# EasyEDA_Schematic.net
KiCad netlist of a schematic drawn in EasyEDA
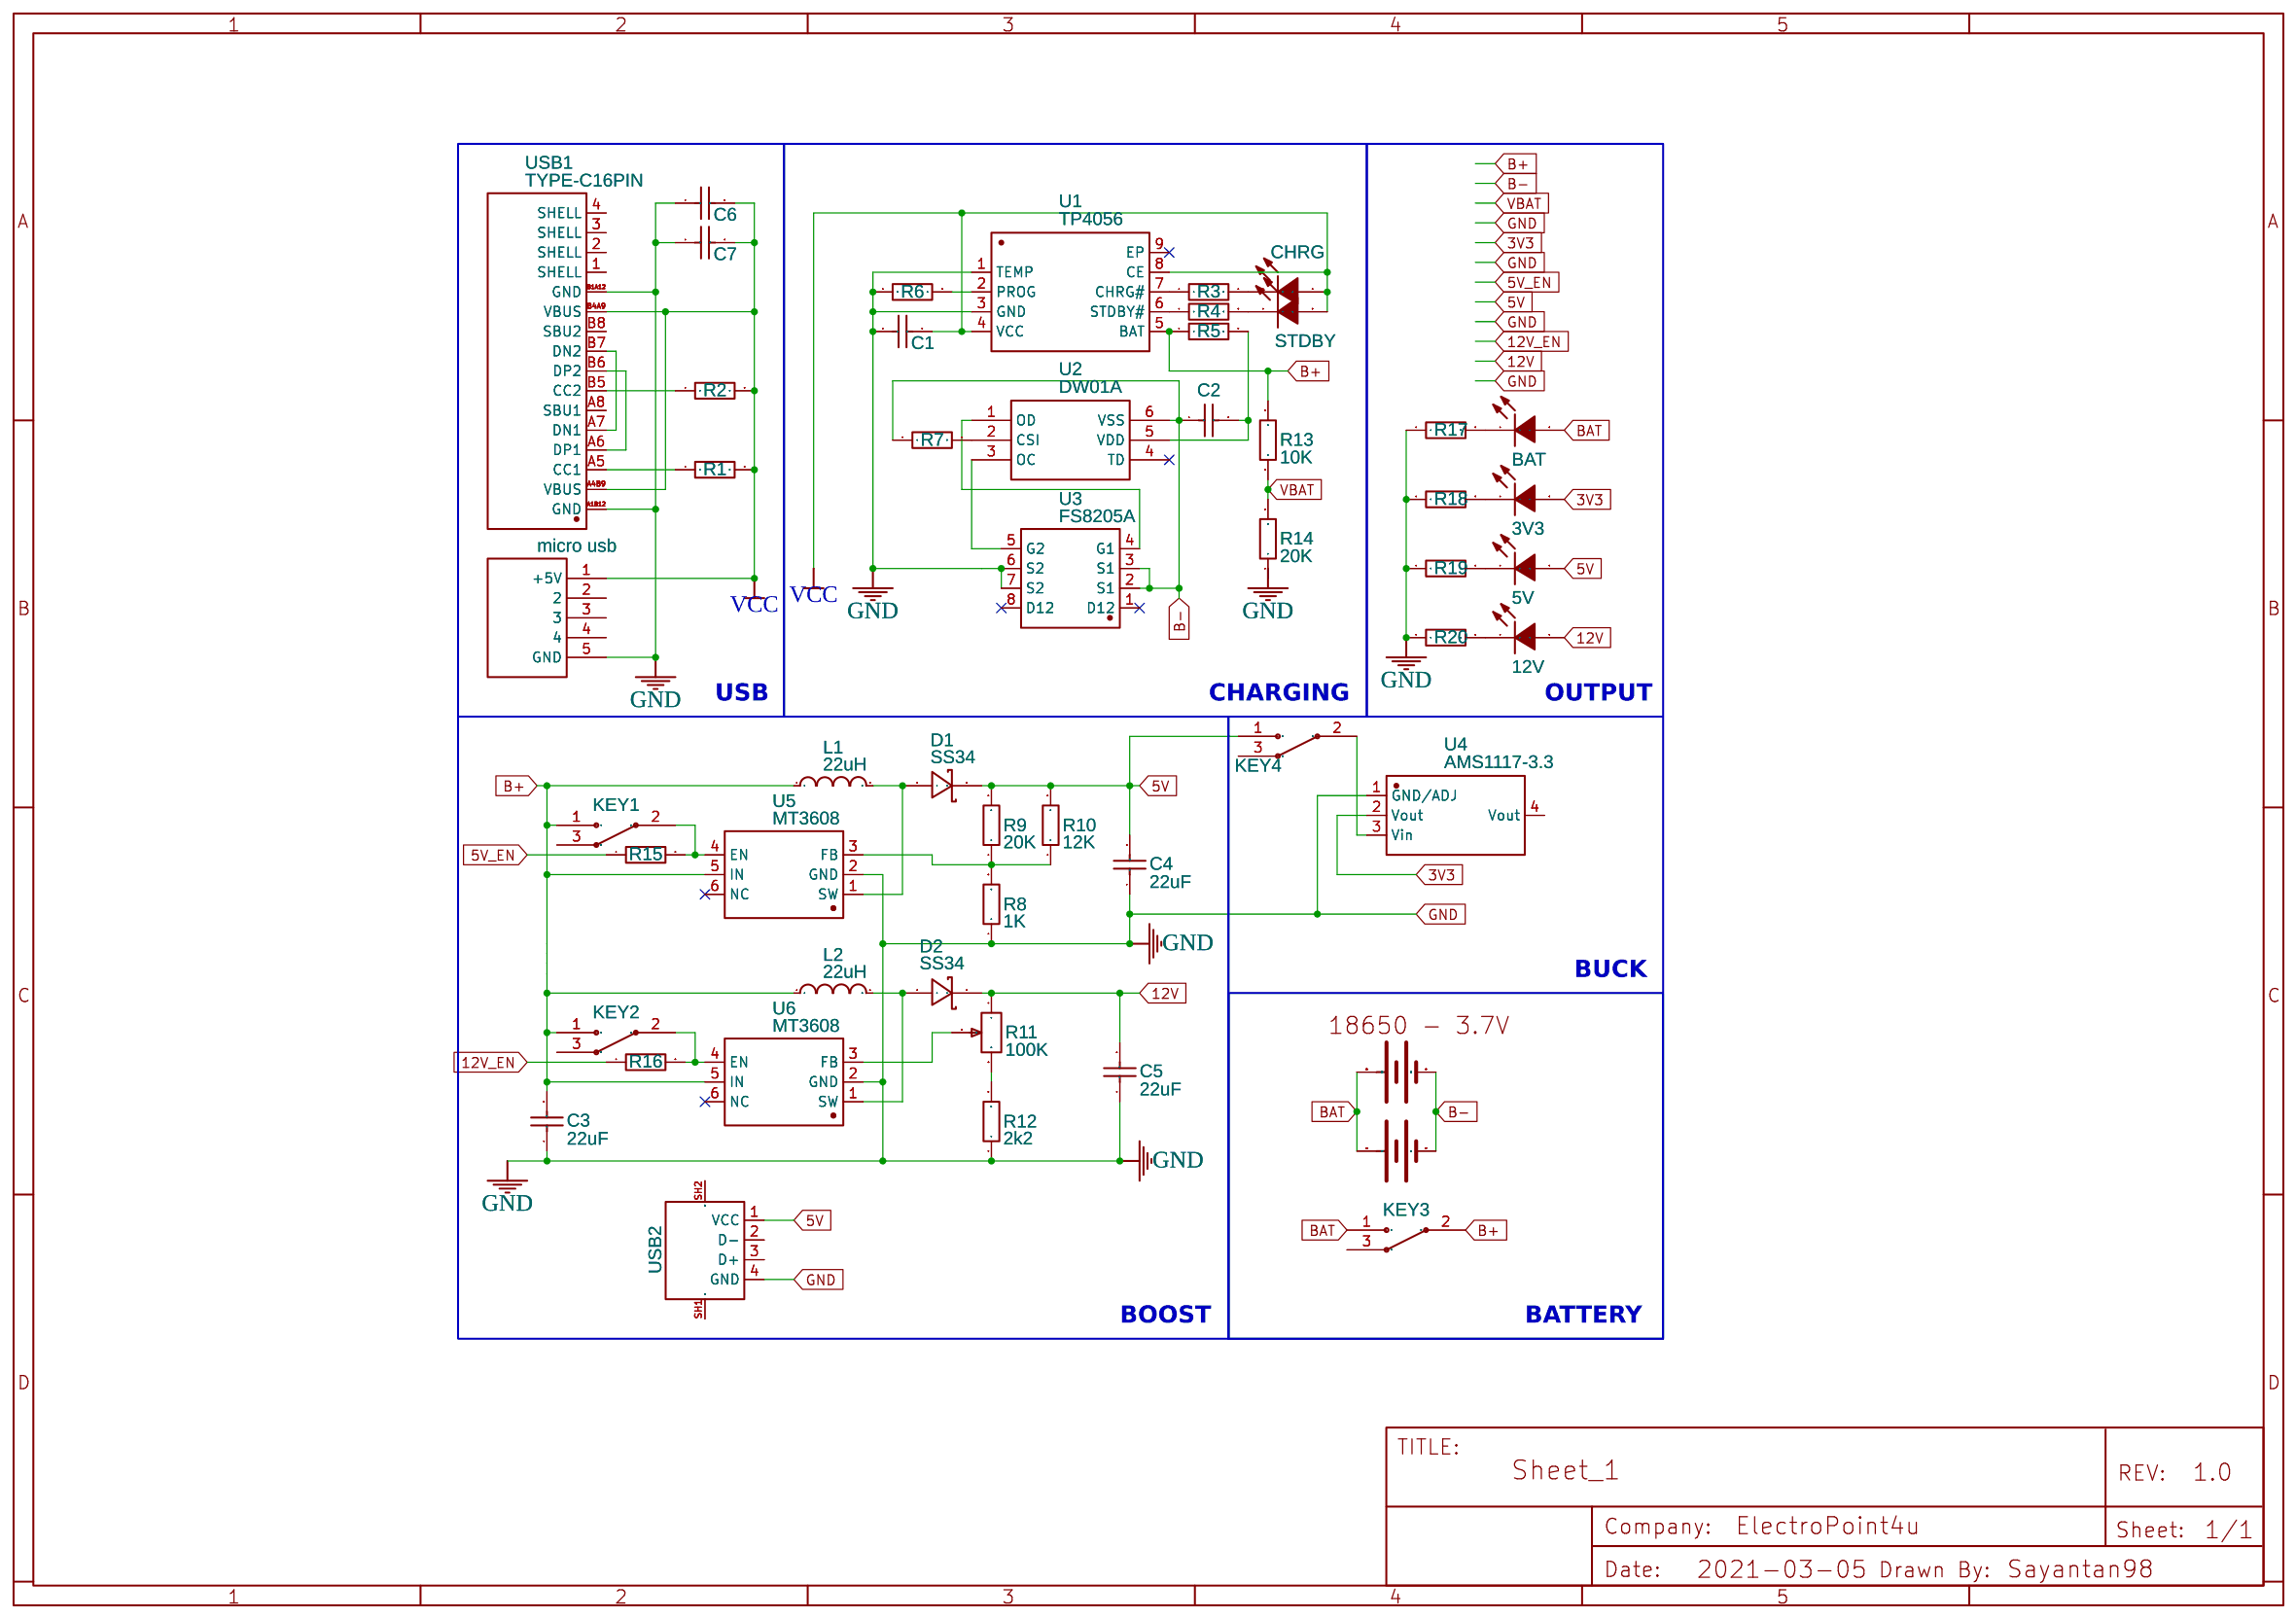
[diagram p0: schematic sheet]

(export (version "E")
  (design (tool "Eeschema 10.0.6"))
  (components
    (comp (ref "3.1V") (value "18650") (libsource (lib "") (part "18650_1")))
    (comp (ref "3.2V") (value "18650") (libsource (lib "") (part "18650")))
    (comp (ref "3V3")
      (value "0805G (Green)")
      (fields (field (name "BOM_Supplier Part") "C2297"))
      (libsource (lib "") (part "0805G (Green)_5"))
    )
    (comp (ref "5V")
      (value "0805G (Green)")
      (fields (field (name "BOM_Supplier Part") "C2297"))
      (libsource (lib "") (part "0805G (Green)_4"))
    )
    (comp (ref "12V")
      (value "0805G (Green)")
      (fields (field (name "BOM_Supplier Part") "C2297"))
      (libsource (lib "") (part "0805G (Green)"))
    )
    (comp (ref "BAT")
      (value "0805G (Green)")
      (fields (field (name "BOM_Supplier Part") "C2297"))
      (libsource (lib "") (part "0805G (Green)_2"))
    )
    (comp (ref "C1")
      (value "10uF")
      (fields
        (field (name "BOM_Manufacturer Part") "CL21A106KAYNNNE")
        (field (name "BOM_Supplier Part") "C15850")
      )
      (libsource (lib "") (part "CL21A106KAYNNNE"))
    )
    (comp (ref "C2")
      (value "100nF")
      (fields
        (field (name "BOM_Manufacturer Part") "CL21B104JBCNNNC")
        (field (name "BOM_Supplier Part") "C62912")
      )
      (libsource (lib "") (part "CL21B104JBCNNNC"))
    )
    (comp (ref "C3")
      (value "22uF")
      (fields
        (field (name "BOM_Manufacturer Part") "CL31A226KPHNNNE")
        (field (name "BOM_Supplier Part") "C5672")
      )
      (libsource (lib "") (part "CL31A226KPHNNNE"))
    )
    (comp (ref "C4")
      (value "22uF")
      (fields
        (field (name "BOM_Manufacturer Part") "CL31A226KPHNNNE")
        (field (name "BOM_Supplier Part") "C5672")
      )
      (libsource (lib "") (part "CL31A226KPHNNNE"))
    )
    (comp (ref "C5")
      (value "22uF")
      (fields
        (field (name "BOM_Manufacturer Part") "CL31A226KPHNNNE")
        (field (name "BOM_Supplier Part") "C5672")
      )
      (libsource (lib "") (part "CL31A226KPHNNNE"))
    )
    (comp (ref "C6")
      (value "10uF")
      (fields
        (field (name "BOM_Manufacturer Part") "CL21A106KAYNNNE")
        (field (name "BOM_Supplier Part") "C15850")
      )
      (libsource (lib "") (part "CL21A106KAYNNNE"))
    )
    (comp (ref "C7")
      (value "1uF")
      (fields
        (field (name "BOM_Manufacturer Part") "CL21A106KAYNNNE")
        (field (name "BOM_Supplier Part") "C15850")
      )
      (libsource (lib "") (part "CL21A106KAYNNNE"))
    )
    (comp (ref "CHRG")
      (value "0805G (Green)")
      (fields (field (name "BOM_Supplier Part") "C2297"))
      (libsource (lib "") (part "0805G (Green)_3"))
    )
    (comp (ref "D1")
      (value "SS34")
      (fields (field (name "BOM_Supplier Part") "C8678"))
      (libsource (lib "") (part "SS34_C8678"))
    )
    (comp (ref "D2")
      (value "SS34")
      (fields (field (name "BOM_Supplier Part") "C8678"))
      (libsource (lib "") (part "SS34_C8678"))
    )
    (comp (ref "KEY1")
      (value "MSK-11027 Toggle Switches")
      (fields (field (name "BOM_Supplier Part") "C21381"))
      (libsource (lib "") (part "MSK-11027 Toggle Switches"))
    )
    (comp (ref "KEY2")
      (value "MSK-11027 Toggle Switches")
      (fields (field (name "BOM_Supplier Part") "C21381"))
      (libsource (lib "") (part "MSK-11027 Toggle Switches"))
    )
    (comp (ref "KEY3")
      (value "MSK-11027 Toggle Switches")
      (fields (field (name "BOM_Supplier Part") "C21381"))
      (libsource (lib "") (part "MSK-11027 Toggle Switches"))
    )
    (comp (ref "KEY4")
      (value "MSK-11027 Toggle Switches")
      (fields (field (name "BOM_Supplier Part") "C21381"))
      (libsource (lib "") (part "MSK-11027 Toggle Switches"))
    )
    (comp (ref "L1")
      (value "22uH")
      (fields
        (field (name "BOM_Manufacturer Part") "SWRB1205S-220MT")
        (field (name "BOM_Supplier Part") "C169385")
      )
      (libsource (lib "") (part "SWRB1205S-220MT"))
    )
    (comp (ref "L2")
      (value "22uH")
      (fields
        (field (name "BOM_Manufacturer Part") "SWRB1205S-220MT")
        (field (name "BOM_Supplier Part") "C169385")
      )
      (libsource (lib "") (part "SWRB1205S-220MT"))
    )
    (comp (ref "R1")
      (value "5.1K")
      (fields
        (field (name "BOM_Manufacturer Part") "0805W8F5101T5E")
        (field (name "BOM_Supplier Part") "C27834")
      )
      (libsource (lib "") (part "0805W8F5101T5E"))
    )
    (comp (ref "R2")
      (value "5.1K")
      (fields
        (field (name "BOM_Manufacturer Part") "0805W8F5101T5E")
        (field (name "BOM_Supplier Part") "C27834")
      )
      (libsource (lib "") (part "0805W8F5101T5E"))
    )
    (comp (ref "R3")
      (value "1K")
      (fields
        (field (name "BOM_Manufacturer Part") "0805WAD1001T5E")
        (field (name "BOM_Supplier Part") "C169072")
      )
      (libsource (lib "") (part "0805WAD1001T5E"))
    )
    (comp (ref "R4")
      (value "1K")
      (fields
        (field (name "BOM_Manufacturer Part") "0805WAD1001T5E")
        (field (name "BOM_Supplier Part") "C169072")
      )
      (libsource (lib "") (part "0805WAD1001T5E"))
    )
    (comp (ref "R5")
      (value "100")
      (fields
        (field (name "BOM_Manufacturer Part") "0805W8F1000T5E")
        (field (name "BOM_Supplier Part") "C17408")
      )
      (libsource (lib "") (part "0805W8F1000T5E"))
    )
    (comp (ref "R6")
      (value "2K")
      (fields
        (field (name "BOM_Manufacturer Part") "0805W8F2001T5E")
        (field (name "BOM_Supplier Part") "C17604")
      )
      (libsource (lib "") (part "0805W8F2001T5E"))
    )
    (comp (ref "R7")
      (value "1K")
      (fields
        (field (name "BOM_Manufacturer Part") "0805WAD1001T5E")
        (field (name "BOM_Supplier Part") "C169072")
      )
      (libsource (lib "") (part "0805WAD1001T5E"))
    )
    (comp (ref "R8")
      (value "1K")
      (fields
        (field (name "BOM_Manufacturer Part") "0805W8F1001T5E")
        (field (name "BOM_Supplier Part") "C17513")
      )
      (libsource (lib "") (part "0805W8F1001T5E"))
    )
    (comp (ref "R9")
      (value "20K")
      (fields
        (field (name "BOM_Manufacturer Part") "0805W8F2002T5E")
        (field (name "BOM_Supplier Part") "C4328")
      )
      (libsource (lib "") (part "0805W8F2002T5E"))
    )
    (comp (ref "R10")
      (value "12K")
      (fields
        (field (name "BOM_Manufacturer Part") "0805W8F1202T5E")
        (field (name "BOM_Supplier Part") "C17444")
      )
      (libsource (lib "") (part "0805W8F1202T5E"))
    )
    (comp (ref "R11") (value "100K") (libsource (lib "") (part "POTENTIOMETER VARIABLE RESISTOR")))
    (comp (ref "R12")
      (value "2k2")
      (fields
        (field (name "BOM_Manufacturer Part") "0805W8F1001T5E")
        (field (name "BOM_Supplier Part") "C17513")
      )
      (libsource (lib "") (part "0805W8F1001T5E"))
    )
    (comp (ref "R13")
      (value "10K")
      (fields
        (field (name "BOM_Manufacturer Part") "TC0550B1002T5E")
        (field (name "BOM_Supplier Part") "C141888")
      )
      (libsource (lib "") (part "TC0550B1002T5E"))
    )
    (comp (ref "R14")
      (value "20K")
      (fields
        (field (name "BOM_Manufacturer Part") "TC0550B1002T5E")
        (field (name "BOM_Supplier Part") "C141888")
      )
      (libsource (lib "") (part "TC0550B1002T5E"))
    )
    (comp (ref "R15")
      (value "100")
      (fields
        (field (name "BOM_Manufacturer Part") "0805W8F1000T5E")
        (field (name "BOM_Supplier Part") "C17408")
      )
      (libsource (lib "") (part "0805W8F1000T5E"))
    )
    (comp (ref "R16")
      (value "100")
      (fields
        (field (name "BOM_Manufacturer Part") "0805W8F1000T5E")
        (field (name "BOM_Supplier Part") "C17408")
      )
      (libsource (lib "") (part "0805W8F1000T5E"))
    )
    (comp (ref "R17")
      (value "1K")
      (fields
        (field (name "BOM_Manufacturer Part") "0805WAD1001T5E")
        (field (name "BOM_Supplier Part") "C169072")
      )
      (libsource (lib "") (part "0805WAD1001T5E"))
    )
    (comp (ref "R18")
      (value "1K")
      (fields
        (field (name "BOM_Manufacturer Part") "0805WAD1001T5E")
        (field (name "BOM_Supplier Part") "C169072")
      )
      (libsource (lib "") (part "0805WAD1001T5E"))
    )
    (comp (ref "R19")
      (value "1K")
      (fields
        (field (name "BOM_Manufacturer Part") "0805WAD1001T5E")
        (field (name "BOM_Supplier Part") "C169072")
      )
      (libsource (lib "") (part "0805WAD1001T5E"))
    )
    (comp (ref "R20")
      (value "1K")
      (fields
        (field (name "BOM_Manufacturer Part") "0805WAD1001T5E")
        (field (name "BOM_Supplier Part") "C169072")
      )
      (libsource (lib "") (part "0805WAD1001T5E"))
    )
    (comp (ref "STDBY")
      (value "0805G (Green)")
      (fields (field (name "BOM_Supplier Part") "C2297"))
      (libsource (lib "") (part "0805G (Green)_1"))
    )
    (comp (ref "U1")
      (value "TP4056")
      (fields (field (name "BOM_Supplier Part") "C382139"))
      (libsource (lib "") (part "TP4056_C382139"))
    )
    (comp (ref "U2")
      (value "DW01A")
      (fields (field (name "BOM_Supplier Part") "C85680"))
      (libsource (lib "") (part "DW01A"))
    )
    (comp (ref "U3")
      (value "FS8205A")
      (fields (field (name "BOM_Supplier Part") "C16052"))
      (libsource (lib "") (part "FS8205A"))
    )
    (comp (ref "U4")
      (value "AMS1117-3.3")
      (fields (field (name "BOM_Supplier Part") "C6186"))
      (libsource (lib "") (part "AMS1117-3.3"))
    )
    (comp (ref "U5")
      (value "MT3608")
      (fields (field (name "BOM_Supplier Part") "C84817"))
      (libsource (lib "") (part "MT3608"))
    )
    (comp (ref "U6")
      (value "MT3608")
      (fields (field (name "BOM_Supplier Part") "C84817"))
      (libsource (lib "") (part "MT3608"))
    )
    (comp (ref "USB1")
      (value "TYPE-C16PIN")
      (fields (field (name "BOM_Supplier Part") "C393939"))
      (libsource (lib "") (part "TYPE-C16PIN"))
    )
    (comp (ref "USB2")
      (value "JTJ-USB-AF-08")
      (fields (field (name "BOM_Supplier Part") "C2345"))
      (libsource (lib "") (part "JTJ-USB-AF-08"))
    )
    (comp (ref "USB3") (value "micro usb") (libsource (lib "") (part "micro usb")))
  )
  (nets
    (net (code "1") (name "3V3") (class "Default")
      (node (ref "3V3") (pin "2") (pinfunction "A_2") (pintype "unspecified"))
      (node (ref "U4") (pin "2") (pinfunction "Vout_2") (pintype "unspecified"))
    )
    (net (code "2") (name "5V") (class "Default")
      (node (ref "5V") (pin "2") (pinfunction "A_2") (pintype "unspecified"))
      (node (ref "C4") (pin "2") (pinfunction "2_2") (pintype "input"))
      (node (ref "D1") (pin "1") (pinfunction "K_1") (pintype "unspecified"))
      (node (ref "KEY4") (pin "1") (pinfunction "1_1") (pintype "unspecified"))
      (node (ref "R10") (pin "2") (pinfunction "2_2") (pintype "input"))
      (node (ref "R9") (pin "2") (pinfunction "2_2") (pintype "input"))
      (node (ref "USB2") (pin "1") (pinfunction "VCC_1") (pintype "input"))
    )
    (net (code "3") (name "5V_EN") (class "Default")
      (node (ref "R15") (pin "1") (pinfunction "1_1") (pintype "input"))
    )
    (net (code "4") (name "12V") (class "Default")
      (node (ref "12V") (pin "2") (pinfunction "A_2") (pintype "unspecified"))
      (node (ref "C5") (pin "2") (pinfunction "2_2") (pintype "input"))
      (node (ref "D2") (pin "1") (pinfunction "K_1") (pintype "unspecified"))
      (node (ref "R11") (pin "1") (pinfunction "1_1") (pintype "input"))
    )
    (net (code "5") (name "12V_EN") (class "Default")
      (node (ref "R16") (pin "1") (pinfunction "1_1") (pintype "input"))
    )
    (net (code "6") (name "B+") (class "Default")
      (node (ref "C3") (pin "2") (pinfunction "2_2") (pintype "input"))
      (node (ref "KEY1") (pin "1") (pinfunction "1_1") (pintype "unspecified"))
      (node (ref "KEY2") (pin "1") (pinfunction "1_1") (pintype "unspecified"))
      (node (ref "KEY3") (pin "2") (pinfunction "2_2") (pintype "unspecified"))
      (node (ref "L1") (pin "1") (pinfunction "1_1") (pintype "unspecified"))
      (node (ref "L2") (pin "1") (pinfunction "1_1") (pintype "unspecified"))
      (node (ref "R13") (pin "2") (pinfunction "2_2") (pintype "unspecified"))
      (node (ref "R5") (pin "1") (pinfunction "1_1") (pintype "input"))
      (node (ref "U1") (pin "5") (pinfunction "BAT_5") (pintype "unspecified"))
      (node (ref "U5") (pin "5") (pinfunction "IN_5") (pintype "unspecified"))
      (node (ref "U6") (pin "5") (pinfunction "IN_5") (pintype "unspecified"))
    )
    (net (code "7") (name "B-") (class "Default")
      (node (ref "3.1V") (pin "GND") (pinfunction "GND_GND") (pintype "passive"))
      (node (ref "3.2V") (pin "GND") (pinfunction "GND_GND") (pintype "passive"))
      (node (ref "C2") (pin "1") (pinfunction "1_1") (pintype "input"))
      (node (ref "R7") (pin "1") (pinfunction "1_1") (pintype "unspecified"))
      (node (ref "U2") (pin "6") (pinfunction "VSS_6") (pintype "unspecified"))
      (node (ref "U3") (pin "2") (pinfunction "S1_2") (pintype "unspecified"))
      (node (ref "U3") (pin "3") (pinfunction "S1_3") (pintype "unspecified"))
    )
    (net (code "8") (name "BAT") (class "Default")
      (node (ref "3.1V") (pin "Positive") (pinfunction "Positive_Positive") (pintype "passive"))
      (node (ref "3.2V") (pin "Positive") (pinfunction "Positive_Positive") (pintype "passive"))
      (node (ref "BAT") (pin "2") (pinfunction "A_2") (pintype "unspecified"))
      (node (ref "KEY3") (pin "1") (pinfunction "1_1") (pintype "unspecified"))
    )
    (net (code "9") (name "GND") (class "Default")
      (node (ref "C1") (pin "1") (pinfunction "1_1") (pintype "input"))
      (node (ref "C3") (pin "1") (pinfunction "1_1") (pintype "input"))
      (node (ref "C4") (pin "1") (pinfunction "1_1") (pintype "input"))
      (node (ref "C5") (pin "1") (pinfunction "1_1") (pintype "input"))
      (node (ref "C6") (pin "1") (pinfunction "1_1") (pintype "input"))
      (node (ref "C7") (pin "1") (pinfunction "1_1") (pintype "input"))
      (node (ref "R12") (pin "1") (pinfunction "1_1") (pintype "input"))
      (node (ref "R14") (pin "1") (pinfunction "1_1") (pintype "unspecified"))
      (node (ref "R17") (pin "1") (pinfunction "1_1") (pintype "unspecified"))
      (node (ref "R18") (pin "1") (pinfunction "1_1") (pintype "unspecified"))
      (node (ref "R19") (pin "1") (pinfunction "1_1") (pintype "unspecified"))
      (node (ref "R20") (pin "1") (pinfunction "1_1") (pintype "unspecified"))
      (node (ref "R6") (pin "1") (pinfunction "1_1") (pintype "input"))
      (node (ref "R8") (pin "1") (pinfunction "1_1") (pintype "input"))
      (node (ref "U1") (pin "1") (pinfunction "TEMP_1") (pintype "unspecified"))
      (node (ref "U1") (pin "3") (pinfunction "GND_3") (pintype "unspecified"))
      (node (ref "U3") (pin "6") (pinfunction "S2_6") (pintype "unspecified"))
      (node (ref "U3") (pin "7") (pinfunction "S2_7") (pintype "unspecified"))
      (node (ref "U4") (pin "1") (pinfunction "GND/ADJ_1") (pintype "unspecified"))
      (node (ref "U5") (pin "2") (pinfunction "GND_2") (pintype "unspecified"))
      (node (ref "U6") (pin "2") (pinfunction "GND_2") (pintype "unspecified"))
      (node (ref "USB1") (pin "A1B12") (pinfunction "GND_A1B12") (pintype "unspecified"))
      (node (ref "USB1") (pin "B1A12") (pinfunction "GND_B1A12") (pintype "unspecified"))
      (node (ref "USB2") (pin "4") (pinfunction "GND_4") (pintype "input"))
      (node (ref "USB3") (pin "5") (pinfunction "GND_5") (pintype "unspecified"))
    )
    (net (code "10") (name "Net-(3V3-K)") (class "Default")
      (node (ref "3V3") (pin "1") (pinfunction "K_1") (pintype "unspecified"))
      (node (ref "R18") (pin "2") (pinfunction "2_2") (pintype "unspecified"))
    )
    (net (code "11") (name "Net-(5V-K)") (class "Default")
      (node (ref "5V") (pin "1") (pinfunction "K_1") (pintype "unspecified"))
      (node (ref "R19") (pin "2") (pinfunction "2_2") (pintype "unspecified"))
    )
    (net (code "12") (name "Net-(12V-K)") (class "Default")
      (node (ref "12V") (pin "1") (pinfunction "K_1") (pintype "unspecified"))
      (node (ref "R20") (pin "2") (pinfunction "2_2") (pintype "unspecified"))
    )
    (net (code "13") (name "Net-(BAT-K)") (class "Default")
      (node (ref "BAT") (pin "1") (pinfunction "K_1") (pintype "unspecified"))
      (node (ref "R17") (pin "2") (pinfunction "2_2") (pintype "unspecified"))
    )
    (net (code "14") (name "Net-(CHRG-K)") (class "Default")
      (node (ref "CHRG") (pin "1") (pinfunction "K_1") (pintype "unspecified"))
      (node (ref "R3") (pin "2") (pinfunction "2_2") (pintype "unspecified"))
    )
    (net (code "15") (name "Net-(D1-A)") (class "Default")
      (node (ref "D1") (pin "2") (pinfunction "A_2") (pintype "unspecified"))
      (node (ref "L1") (pin "2") (pinfunction "2_2") (pintype "unspecified"))
      (node (ref "U5") (pin "1") (pinfunction "SW_1") (pintype "unspecified"))
    )
    (net (code "16") (name "Net-(D2-A)") (class "Default")
      (node (ref "D2") (pin "2") (pinfunction "A_2") (pintype "unspecified"))
      (node (ref "L2") (pin "2") (pinfunction "2_2") (pintype "unspecified"))
      (node (ref "U6") (pin "1") (pinfunction "SW_1") (pintype "unspecified"))
    )
    (net (code "17") (name "Net-(R11-Pad3)") (class "Default")
      (node (ref "R11") (pin "3") (pinfunction "3_3") (pintype "input"))
      (node (ref "R12") (pin "2") (pinfunction "2_2") (pintype "input"))
    )
    (net (code "18") (name "Net-(STDBY-K)") (class "Default")
      (node (ref "R4") (pin "2") (pinfunction "2_2") (pintype "unspecified"))
      (node (ref "STDBY") (pin "1") (pinfunction "K_1") (pintype "unspecified"))
    )
    (net (code "19") (name "Net-(U1-CHRG#)") (class "Default")
      (node (ref "R3") (pin "1") (pinfunction "1_1") (pintype "unspecified"))
      (node (ref "U1") (pin "7") (pinfunction "CHRG#_7") (pintype "unspecified"))
    )
    (net (code "20") (name "Net-(U1-PROG)") (class "Default")
      (node (ref "R6") (pin "2") (pinfunction "2_2") (pintype "input"))
      (node (ref "U1") (pin "2") (pinfunction "PROG_2") (pintype "unspecified"))
    )
    (net (code "21") (name "Net-(U1-STDBY#)") (class "Default")
      (node (ref "R4") (pin "1") (pinfunction "1_1") (pintype "unspecified"))
      (node (ref "U1") (pin "6") (pinfunction "STDBY#_6") (pintype "unspecified"))
    )
    (net (code "22") (name "Net-(U2-CSI)") (class "Default")
      (node (ref "R7") (pin "2") (pinfunction "2_2") (pintype "unspecified"))
      (node (ref "U2") (pin "2") (pinfunction "CSI_2") (pintype "unspecified"))
    )
    (net (code "23") (name "Net-(U2-OC)") (class "Default")
      (node (ref "U2") (pin "3") (pinfunction "OC_3") (pintype "unspecified"))
      (node (ref "U3") (pin "5") (pinfunction "G2_5") (pintype "unspecified"))
    )
    (net (code "24") (name "Net-(U2-OD)") (class "Default")
      (node (ref "U2") (pin "1") (pinfunction "OD_1") (pintype "unspecified"))
      (node (ref "U3") (pin "4") (pinfunction "G1_4") (pintype "unspecified"))
    )
    (net (code "25") (name "Net-(U2-VDD)") (class "Default")
      (node (ref "C2") (pin "2") (pinfunction "2_2") (pintype "input"))
      (node (ref "R5") (pin "2") (pinfunction "2_2") (pintype "input"))
      (node (ref "U2") (pin "5") (pinfunction "VDD_5") (pintype "unspecified"))
    )
    (net (code "26") (name "Net-(U4-Vin)") (class "Default")
      (node (ref "KEY4") (pin "2") (pinfunction "2_2") (pintype "unspecified"))
      (node (ref "U4") (pin "3") (pinfunction "Vin_3") (pintype "unspecified"))
    )
    (net (code "27") (name "Net-(U5-EN)") (class "Default")
      (node (ref "KEY1") (pin "2") (pinfunction "2_2") (pintype "unspecified"))
      (node (ref "R15") (pin "2") (pinfunction "2_2") (pintype "input"))
      (node (ref "U5") (pin "4") (pinfunction "EN_4") (pintype "unspecified"))
    )
    (net (code "28") (name "Net-(U5-FB)") (class "Default")
      (node (ref "R10") (pin "1") (pinfunction "1_1") (pintype "input"))
      (node (ref "R8") (pin "2") (pinfunction "2_2") (pintype "input"))
      (node (ref "R9") (pin "1") (pinfunction "1_1") (pintype "input"))
      (node (ref "U5") (pin "3") (pinfunction "FB_3") (pintype "unspecified"))
    )
    (net (code "29") (name "Net-(U6-EN)") (class "Default")
      (node (ref "KEY2") (pin "2") (pinfunction "2_2") (pintype "unspecified"))
      (node (ref "R16") (pin "2") (pinfunction "2_2") (pintype "input"))
      (node (ref "U6") (pin "4") (pinfunction "EN_4") (pintype "unspecified"))
    )
    (net (code "30") (name "Net-(U6-FB)") (class "Default")
      (node (ref "R11") (pin "2") (pinfunction "2_2") (pintype "input"))
      (node (ref "U6") (pin "3") (pinfunction "FB_3") (pintype "unspecified"))
    )
    (net (code "31") (name "Net-(USB1-CC1)") (class "Default")
      (node (ref "R1") (pin "1") (pinfunction "1_1") (pintype "input"))
      (node (ref "USB1") (pin "A5") (pinfunction "CC1_A5") (pintype "unspecified"))
    )
    (net (code "32") (name "Net-(USB1-CC2)") (class "Default")
      (node (ref "R2") (pin "1") (pinfunction "1_1") (pintype "input"))
      (node (ref "USB1") (pin "B5") (pinfunction "CC2_B5") (pintype "unspecified"))
    )
    (net (code "33") (name "Net-(USB1-DN1)") (class "Default")
      (node (ref "USB1") (pin "A7") (pinfunction "DN1_A7") (pintype "unspecified"))
      (node (ref "USB1") (pin "B7") (pinfunction "DN2_B7") (pintype "unspecified"))
    )
    (net (code "34") (name "Net-(USB1-DP1)") (class "Default")
      (node (ref "USB1") (pin "A6") (pinfunction "DP1_A6") (pintype "unspecified"))
      (node (ref "USB1") (pin "B6") (pinfunction "DP2_B6") (pintype "unspecified"))
    )
    (net (code "35") (name "VBAT") (class "Default")
      (node (ref "R13") (pin "1") (pinfunction "1_1") (pintype "unspecified"))
      (node (ref "R14") (pin "2") (pinfunction "2_2") (pintype "unspecified"))
    )
    (net (code "36") (name "VCC") (class "Default")
      (node (ref "C1") (pin "2") (pinfunction "2_2") (pintype "input"))
      (node (ref "C6") (pin "2") (pinfunction "2_2") (pintype "input"))
      (node (ref "C7") (pin "2") (pinfunction "2_2") (pintype "input"))
      (node (ref "CHRG") (pin "2") (pinfunction "A_2") (pintype "unspecified"))
      (node (ref "R1") (pin "2") (pinfunction "2_2") (pintype "input"))
      (node (ref "R2") (pin "2") (pinfunction "2_2") (pintype "input"))
      (node (ref "STDBY") (pin "2") (pinfunction "A_2") (pintype "unspecified"))
      (node (ref "U1") (pin "4") (pinfunction "VCC_4") (pintype "unspecified"))
      (node (ref "U1") (pin "8") (pinfunction "CE_8") (pintype "unspecified"))
      (node (ref "USB1") (pin "A4B9") (pinfunction "VBUS_A4B9") (pintype "unspecified"))
      (node (ref "USB1") (pin "B4A9") (pinfunction "VBUS_B4A9") (pintype "unspecified"))
      (node (ref "USB3") (pin "1") (pinfunction "+5V_1") (pintype "unspecified"))
    )
    (net (code "37") (name "unconnected-(KEY1-Pad3)") (class "Default")
      (node (ref "KEY1") (pin "3") (pinfunction "3_3") (pintype "unspecified"))
    )
    (net (code "38") (name "unconnected-(KEY2-Pad3)") (class "Default")
      (node (ref "KEY2") (pin "3") (pinfunction "3_3") (pintype "unspecified"))
    )
    (net (code "39") (name "unconnected-(KEY3-Pad3)") (class "Default")
      (node (ref "KEY3") (pin "3") (pinfunction "3_3") (pintype "unspecified"))
    )
    (net (code "40") (name "unconnected-(KEY4-Pad3)") (class "Default")
      (node (ref "KEY4") (pin "3") (pinfunction "3_3") (pintype "unspecified"))
    )
    (net (code "41") (name "unconnected-(U1-EP-Pad9)") (class "Default")
      (node (ref "U1") (pin "9") (pinfunction "EP_9") (pintype "unspecified+no_connect"))
    )
    (net (code "42") (name "unconnected-(U2-TD-Pad4)") (class "Default")
      (node (ref "U2") (pin "4") (pinfunction "TD_4") (pintype "unspecified+no_connect"))
    )
    (net (code "43") (name "unconnected-(U3-D12-Pad1)") (class "Default")
      (node (ref "U3") (pin "1") (pinfunction "D12_1") (pintype "unspecified+no_connect"))
    )
    (net (code "44") (name "unconnected-(U3-D12-Pad8)") (class "Default")
      (node (ref "U3") (pin "8") (pinfunction "D12_8") (pintype "unspecified+no_connect"))
    )
    (net (code "45") (name "unconnected-(U4-Vout-Pad4)") (class "Default")
      (node (ref "U4") (pin "4") (pinfunction "Vout_4") (pintype "unspecified"))
    )
    (net (code "46") (name "unconnected-(U5-NC-Pad6)") (class "Default")
      (node (ref "U5") (pin "6") (pinfunction "NC_6") (pintype "unspecified+no_connect"))
    )
    (net (code "47") (name "unconnected-(U6-NC-Pad6)") (class "Default")
      (node (ref "U6") (pin "6") (pinfunction "NC_6") (pintype "unspecified+no_connect"))
    )
    (net (code "48") (name "unconnected-(USB1-SBU1-PadA8)") (class "Default")
      (node (ref "USB1") (pin "A8") (pinfunction "SBU1_A8") (pintype "unspecified"))
    )
    (net (code "49") (name "unconnected-(USB1-SBU2-PadB8)") (class "Default")
      (node (ref "USB1") (pin "B8") (pinfunction "SBU2_B8") (pintype "unspecified"))
    )
    (net (code "50") (name "unconnected-(USB1-SHELL-Pad1)") (class "Default")
      (node (ref "USB1") (pin "1") (pinfunction "SHELL_1") (pintype "unspecified"))
    )
    (net (code "51") (name "unconnected-(USB1-SHELL-Pad2)") (class "Default")
      (node (ref "USB1") (pin "2") (pinfunction "SHELL_2") (pintype "unspecified"))
    )
    (net (code "52") (name "unconnected-(USB1-SHELL-Pad3)") (class "Default")
      (node (ref "USB1") (pin "3") (pinfunction "SHELL_3") (pintype "unspecified"))
    )
    (net (code "53") (name "unconnected-(USB1-SHELL-Pad4)") (class "Default")
      (node (ref "USB1") (pin "4") (pinfunction "SHELL_4") (pintype "unspecified"))
    )
    (net (code "54") (name "unconnected-(USB2-D+-Pad3)") (class "Default")
      (node (ref "USB2") (pin "3") (pinfunction "D+_3") (pintype "input"))
    )
    (net (code "55") (name "unconnected-(USB2-D--Pad2)") (class "Default")
      (node (ref "USB2") (pin "2") (pinfunction "D-_2") (pintype "input"))
    )
    (net (code "56") (name "unconnected-(USB2-PadSH1)") (class "Default")
      (node (ref "USB2") (pin "SH1") (pinfunction "SH1_SH1") (pintype "unspecified"))
    )
    (net (code "57") (name "unconnected-(USB2-PadSH2)") (class "Default")
      (node (ref "USB2") (pin "SH2") (pinfunction "SH2_SH2") (pintype "unspecified"))
    )
    (net (code "58") (name "unconnected-(USB3-Pad2)") (class "Default")
      (node (ref "USB3") (pin "2") (pinfunction "2_2") (pintype "unspecified"))
    )
    (net (code "59") (name "unconnected-(USB3-Pad3)") (class "Default")
      (node (ref "USB3") (pin "3") (pinfunction "3_3") (pintype "unspecified"))
    )
    (net (code "60") (name "unconnected-(USB3-Pad4)") (class "Default")
      (node (ref "USB3") (pin "4") (pinfunction "4_4") (pintype "unspecified"))
    )
  )
)
